# ReflowMaster.net
KiCad netlist of a schematic drawn in EAGLE
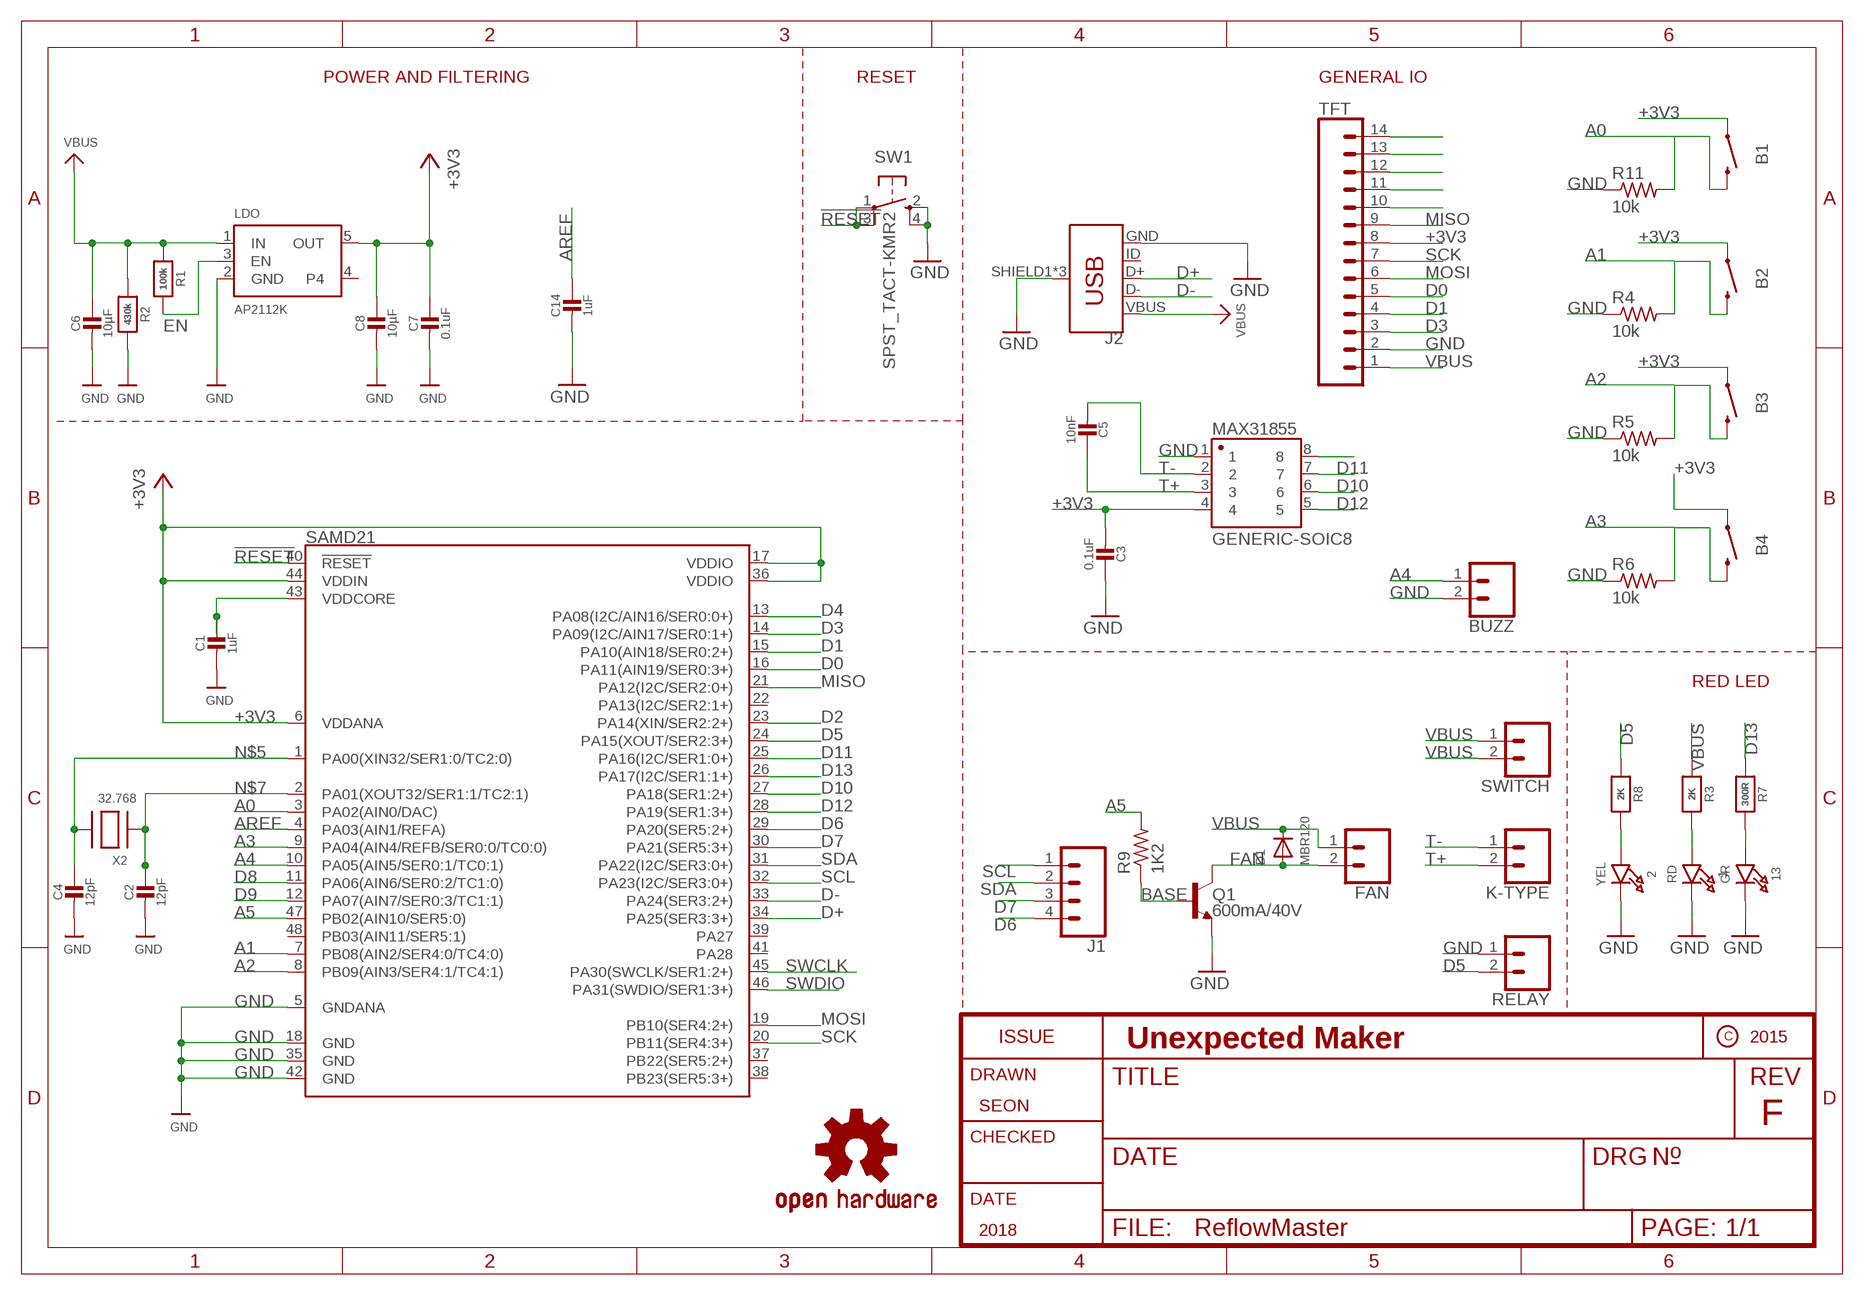
[diagram p0: schematic, sheet 1]

(export (version "E")
  (design (tool "Eeschema 10.0.6"))
  (components
    (comp (ref "1")
      (value "RD")
      (footprint "eagle-import:CHIPLED_0805_NOOUTLINE")
      (libsource (lib "eagle-import") (part "LED0805_NOOUTLINE"))
    )
    (comp (ref "2")
      (value "YEL")
      (footprint "eagle-import:CHIPLED_0805_NOOUTLINE")
      (libsource (lib "eagle-import") (part "LED0805_NOOUTLINE"))
    )
    (comp (ref "13")
      (value "GR")
      (footprint "eagle-import:CHIPLED_0805_NOOUTLINE")
      (libsource (lib "eagle-import") (part "LED0805_NOOUTLINE"))
    )
    (comp (ref "B1")
      (value "MOMENTARY-SWITCH-SPST-PTH-RIGHT-ANGLE-KIT")
      (footprint "eagle-import:TACTILE_SWITCH_PTH_RIGHT_ANGLE_KIT")
      (libsource (lib "eagle-import") (part "MOMENTARY-SWITCH-SPST-PTH-RIGHT-ANGLE-KIT"))
    )
    (comp (ref "B2")
      (value "MOMENTARY-SWITCH-SPST-PTH-RIGHT-ANGLE-KIT")
      (footprint "eagle-import:TACTILE_SWITCH_PTH_RIGHT_ANGLE_KIT")
      (libsource (lib "eagle-import") (part "MOMENTARY-SWITCH-SPST-PTH-RIGHT-ANGLE-KIT"))
    )
    (comp (ref "B3")
      (value "MOMENTARY-SWITCH-SPST-PTH-RIGHT-ANGLE-KIT")
      (footprint "eagle-import:TACTILE_SWITCH_PTH_RIGHT_ANGLE_KIT")
      (libsource (lib "eagle-import") (part "MOMENTARY-SWITCH-SPST-PTH-RIGHT-ANGLE-KIT"))
    )
    (comp (ref "B4")
      (value "MOMENTARY-SWITCH-SPST-PTH-RIGHT-ANGLE-KIT")
      (footprint "eagle-import:TACTILE_SWITCH_PTH_RIGHT_ANGLE_KIT")
      (libsource (lib "eagle-import") (part "MOMENTARY-SWITCH-SPST-PTH-RIGHT-ANGLE-KIT"))
    )
    (comp (ref "BUZZ")
      (value "CONN_02")
      (footprint "eagle-import:1X02")
      (libsource (lib "eagle-import") (part "CONN_02"))
    )
    (comp (ref "C1")
      (value "1uF")
      (footprint "eagle-import:0805-NO")
      (libsource (lib "eagle-import") (part "CAP_CERAMIC0805-NOOUTLINE"))
    )
    (comp (ref "C2")
      (value "12pF")
      (footprint "eagle-import:0805-NO")
      (libsource (lib "eagle-import") (part "CAP_CERAMIC0805-NOOUTLINE"))
    )
    (comp (ref "C3")
      (value "0.1uF")
      (footprint "eagle-import:0805-NO")
      (libsource (lib "eagle-import") (part "CAP_CERAMIC0805-NOOUTLINE"))
    )
    (comp (ref "C4")
      (value "12pF")
      (footprint "eagle-import:0805-NO")
      (libsource (lib "eagle-import") (part "CAP_CERAMIC0805-NOOUTLINE"))
    )
    (comp (ref "C5")
      (value "10nF")
      (footprint "eagle-import:0805-NO")
      (libsource (lib "eagle-import") (part "CAP_CERAMIC0805-NOOUTLINE"))
    )
    (comp (ref "C6")
      (value "10µF")
      (footprint "eagle-import:0805-NO")
      (libsource (lib "eagle-import") (part "CAP_CERAMIC0805-NOOUTLINE"))
    )
    (comp (ref "C7")
      (value "0.1uF")
      (footprint "eagle-import:0805-NO")
      (libsource (lib "eagle-import") (part "CAP_CERAMIC0805-NOOUTLINE"))
    )
    (comp (ref "C8")
      (value "10µF")
      (footprint "eagle-import:0805-NO")
      (libsource (lib "eagle-import") (part "CAP_CERAMIC0805-NOOUTLINE"))
    )
    (comp (ref "C14")
      (value "1uF")
      (footprint "eagle-import:0805-NO")
      (libsource (lib "eagle-import") (part "CAP_CERAMIC0805-NOOUTLINE"))
    )
    (comp (ref "D1")
      (value "MBR120")
      (footprint "eagle-import:SOD-123")
      (libsource (lib "eagle-import") (part "DIODESOD-123"))
    )
    (comp (ref "FAN")
      (value "CONN_02")
      (footprint "eagle-import:1X02")
      (libsource (lib "eagle-import") (part "CONN_02"))
    )
    (comp (ref "J1")
      (value "CONN_041X04_NO_SILK")
      (footprint "eagle-import:1X04_NO_SILK")
      (libsource (lib "eagle-import") (part "CONN_041X04_NO_SILK"))
    )
    (comp (ref "J2")
      (value "USB_MICRO-B_FEMALE-SMT")
      (footprint "eagle-import:USB-B-MICRO-SMD")
      (libsource (lib "eagle-import") (part "USB_MICRO-B_FEMALE-SMT"))
    )
    (comp (ref "K-TYPE")
      (value "CONN_02")
      (footprint "eagle-import:1X02")
      (libsource (lib "eagle-import") (part "CONN_02"))
    )
    (comp (ref "LDO")
      (value "AP2112K")
      (footprint "eagle-import:SOT23-5")
      (libsource (lib "eagle-import") (part "VREG_SOT23-5"))
    )
    (comp (ref "LOGO1")
      (value "OSHW-LOGOS")
      (footprint "eagle-import:OSHW-LOGO-S")
      (libsource (lib "eagle-import") (part "OSHW-LOGOS"))
    )
    (comp (ref "MAX31855")
      (value "GENERIC-SOIC8")
      (footprint "eagle-import:SO08-UNIVERSAL")
      (libsource (lib "eagle-import") (part "GENERIC-SOIC8"))
    )
    (comp (ref "Q1")
      (value "600mA/40V")
      (footprint "eagle-import:SOT23-3")
      (libsource (lib "eagle-import") (part "TRANS_NPN-MMBT2222AL"))
    )
    (comp (ref "R1")
      (value "100k")
      (footprint "eagle-import:0805-NO")
      (libsource (lib "eagle-import") (part "RESISTOR0805_NOOUTLINE"))
    )
    (comp (ref "R2")
      (value "430k")
      (footprint "eagle-import:0805-NO")
      (libsource (lib "eagle-import") (part "RESISTOR0805_NOOUTLINE"))
    )
    (comp (ref "R3")
      (value "2K")
      (footprint "eagle-import:0805-NO")
      (libsource (lib "eagle-import") (part "RESISTOR0805_NOOUTLINE"))
    )
    (comp (ref "R4")
      (value "10k")
      (footprint "eagle-import:R0805")
      (libsource (lib "eagle-import") (part "R-US_R0805"))
    )
    (comp (ref "R5")
      (value "10k")
      (footprint "eagle-import:R0805")
      (libsource (lib "eagle-import") (part "R-US_R0805"))
    )
    (comp (ref "R6")
      (value "10k")
      (footprint "eagle-import:R0805")
      (libsource (lib "eagle-import") (part "R-US_R0805"))
    )
    (comp (ref "R7")
      (value "300R")
      (footprint "eagle-import:0805-NO")
      (libsource (lib "eagle-import") (part "RESISTOR0805_NOOUTLINE"))
    )
    (comp (ref "R8")
      (value "2K")
      (footprint "eagle-import:0805-NO")
      (libsource (lib "eagle-import") (part "RESISTOR0805_NOOUTLINE"))
    )
    (comp (ref "R9")
      (value "1K2")
      (footprint "eagle-import:R0805")
      (libsource (lib "eagle-import") (part "R-US_R0805"))
    )
    (comp (ref "R11")
      (value "10k")
      (footprint "eagle-import:R0805")
      (libsource (lib "eagle-import") (part "R-US_R0805"))
    )
    (comp (ref "RELAY")
      (value "CONN_02")
      (footprint "eagle-import:1X02")
      (libsource (lib "eagle-import") (part "CONN_02"))
    )
    (comp (ref "SAMD21")
      (value "ATSAMD21G-A")
      (footprint "eagle-import:TQFP-48")
      (libsource (lib "eagle-import") (part "ATSAMD21G-A"))
    )
    (comp (ref "SW1")
      (value "SPST_TACT-KMR2")
      (footprint "eagle-import:KMR2")
      (libsource (lib "eagle-import") (part "SPST_TACT-KMR2"))
    )
    (comp (ref "SWITCH")
      (value "CONN_02")
      (footprint "eagle-import:1X02")
      (libsource (lib "eagle-import") (part "CONN_02"))
    )
    (comp (ref "TFT")
      (value "CONN_14NO_SILK")
      (footprint "eagle-import:1X14_NO_SILK")
      (libsource (lib "eagle-import") (part "CONN_14NO_SILK"))
    )
    (comp (ref "X2")
      (value "32.768")
      (footprint "eagle-import:XTAL3215")
      (libsource (lib "eagle-import") (part "XTAL-3.2X1.5"))
    )
  )
  (nets
    (net (code "1") (name "+3V3") (class "Default")
      (node (ref "B1") (pin "1") (pinfunction "1_1") (pintype "passive"))
      (node (ref "B2") (pin "1") (pinfunction "1_1") (pintype "passive"))
      (node (ref "B3") (pin "1") (pinfunction "1_1") (pintype "passive"))
      (node (ref "B4") (pin "1") (pinfunction "1_1") (pintype "passive"))
      (node (ref "C3") (pin "2") (pinfunction "2_2") (pintype "passive"))
      (node (ref "C7") (pin "1") (pinfunction "1_1") (pintype "passive"))
      (node (ref "C8") (pin "1") (pinfunction "1_1") (pintype "passive"))
      (node (ref "LDO") (pin "5") (pinfunction "OUT_5") (pintype "power_in"))
      (node (ref "MAX31855") (pin "4") (pinfunction "4_4") (pintype "bidirectional"))
      (node (ref "SAMD21") (pin "17") (pinfunction "VDDIO_17") (pintype "bidirectional"))
      (node (ref "SAMD21") (pin "36") (pinfunction "VDDIO_36") (pintype "bidirectional"))
      (node (ref "SAMD21") (pin "44") (pinfunction "VDDIN_44") (pintype "bidirectional"))
      (node (ref "SAMD21") (pin "6") (pinfunction "VDDANA_6") (pintype "bidirectional"))
      (node (ref "TFT") (pin "8") (pinfunction "8_8") (pintype "passive"))
    )
    (net (code "2") (name "/A0") (class "Default")
      (node (ref "B1") (pin "2") (pinfunction "2_2") (pintype "passive"))
      (node (ref "R11") (pin "2") (pinfunction "2_2") (pintype "passive"))
      (node (ref "SAMD21") (pin "3") (pinfunction "PA02(AIN0/DAC)_3") (pintype "bidirectional"))
    )
    (net (code "3") (name "/A1") (class "Default")
      (node (ref "B2") (pin "2") (pinfunction "2_2") (pintype "passive"))
      (node (ref "R4") (pin "2") (pinfunction "2_2") (pintype "passive"))
      (node (ref "SAMD21") (pin "7") (pinfunction "PB08(AIN2/SER4:0/TC4:0)_7") (pintype "bidirectional"))
    )
    (net (code "4") (name "/A2") (class "Default")
      (node (ref "B3") (pin "2") (pinfunction "2_2") (pintype "passive"))
      (node (ref "R5") (pin "2") (pinfunction "2_2") (pintype "passive"))
      (node (ref "SAMD21") (pin "8") (pinfunction "PB09(AIN3/SER4:1/TC4:1)_8") (pintype "bidirectional"))
    )
    (net (code "5") (name "/A3") (class "Default")
      (node (ref "B4") (pin "2") (pinfunction "2_2") (pintype "passive"))
      (node (ref "R6") (pin "2") (pinfunction "2_2") (pintype "passive"))
      (node (ref "SAMD21") (pin "9") (pinfunction "PA04(AIN4/REFB/SER0:0/TC0:0)_9") (pintype "bidirectional"))
    )
    (net (code "6") (name "/A4") (class "Default")
      (node (ref "BUZZ") (pin "1") (pinfunction "1_1") (pintype "passive"))
      (node (ref "SAMD21") (pin "10") (pinfunction "PA05(AIN5/SER0:1/TC0:1)_10") (pintype "bidirectional"))
    )
    (net (code "7") (name "/A5") (class "Default")
      (node (ref "R9") (pin "2") (pinfunction "2_2") (pintype "passive"))
      (node (ref "SAMD21") (pin "47") (pinfunction "PB02(AIN10/SER5:0)_47") (pintype "bidirectional"))
    )
    (net (code "8") (name "/AREF") (class "Default")
      (node (ref "C14") (pin "1") (pinfunction "1_1") (pintype "passive"))
      (node (ref "SAMD21") (pin "4") (pinfunction "PA03(AIN1/REFA)_4") (pintype "bidirectional"))
    )
    (net (code "9") (name "/BASE") (class "Default")
      (node (ref "Q1") (pin "1") (pinfunction "B_1") (pintype "passive"))
      (node (ref "R9") (pin "1") (pinfunction "1_1") (pintype "passive"))
    )
    (net (code "10") (name "/D+") (class "Default")
      (node (ref "J2") (pin "D+") (pinfunction "D+_D+") (pintype "bidirectional"))
      (node (ref "SAMD21") (pin "34") (pinfunction "PA25(SER3:3+)_34") (pintype "bidirectional"))
    )
    (net (code "11") (name "/D-") (class "Default")
      (node (ref "J2") (pin "D-") (pinfunction "D-_D-") (pintype "bidirectional"))
      (node (ref "SAMD21") (pin "33") (pinfunction "PA24(SER3:2+)_33") (pintype "bidirectional"))
    )
    (net (code "12") (name "/D0") (class "Default")
      (node (ref "SAMD21") (pin "16") (pinfunction "PA11(AIN19/SER0:3+)_16") (pintype "bidirectional"))
      (node (ref "TFT") (pin "5") (pinfunction "5_5") (pintype "passive"))
    )
    (net (code "13") (name "/D1") (class "Default")
      (node (ref "SAMD21") (pin "15") (pinfunction "PA10(AIN18/SER0:2+)_15") (pintype "bidirectional"))
      (node (ref "TFT") (pin "4") (pinfunction "4_4") (pintype "passive"))
    )
    (net (code "14") (name "/D2") (class "Default")
      (node (ref "SAMD21") (pin "23") (pinfunction "PA14(XIN/SER2:2+)_23") (pintype "bidirectional"))
    )
    (net (code "15") (name "/D3") (class "Default")
      (node (ref "SAMD21") (pin "14") (pinfunction "PA09(I2C/AIN17/SER0:1+)_14") (pintype "bidirectional"))
      (node (ref "TFT") (pin "3") (pinfunction "3_3") (pintype "passive"))
    )
    (net (code "16") (name "/D4") (class "Default")
      (node (ref "SAMD21") (pin "13") (pinfunction "PA08(I2C/AIN16/SER0:0+)_13") (pintype "bidirectional"))
    )
    (net (code "17") (name "/D5") (class "Default")
      (node (ref "R8") (pin "1") (pinfunction "1_1") (pintype "passive"))
      (node (ref "RELAY") (pin "2") (pinfunction "2_2") (pintype "passive"))
      (node (ref "SAMD21") (pin "24") (pinfunction "PA15(XOUT/SER2:3+)_24") (pintype "bidirectional"))
    )
    (net (code "18") (name "/D6") (class "Default")
      (node (ref "J1") (pin "4") (pinfunction "4_4") (pintype "passive"))
      (node (ref "SAMD21") (pin "29") (pinfunction "PA20(SER5:2+)_29") (pintype "bidirectional"))
    )
    (net (code "19") (name "/D7") (class "Default")
      (node (ref "J1") (pin "3") (pinfunction "3_3") (pintype "passive"))
      (node (ref "SAMD21") (pin "30") (pinfunction "PA21(SER5:3+)_30") (pintype "bidirectional"))
    )
    (net (code "20") (name "/D8") (class "Default")
      (node (ref "SAMD21") (pin "11") (pinfunction "PA06(AIN6/SER0:2/TC1:0)_11") (pintype "bidirectional"))
    )
    (net (code "21") (name "/D9") (class "Default")
      (node (ref "SAMD21") (pin "12") (pinfunction "PA07(AIN7/SER0:3/TC1:1)_12") (pintype "bidirectional"))
    )
    (net (code "22") (name "/D10") (class "Default")
      (node (ref "MAX31855") (pin "6") (pinfunction "6_6") (pintype "bidirectional"))
      (node (ref "SAMD21") (pin "27") (pinfunction "PA18(SER1:2+)_27") (pintype "bidirectional"))
    )
    (net (code "23") (name "/D11") (class "Default")
      (node (ref "MAX31855") (pin "7") (pinfunction "7_7") (pintype "bidirectional"))
      (node (ref "SAMD21") (pin "25") (pinfunction "PA16(I2C/SER1:0+)_25") (pintype "bidirectional"))
    )
    (net (code "24") (name "/D12") (class "Default")
      (node (ref "MAX31855") (pin "5") (pinfunction "5_5") (pintype "bidirectional"))
      (node (ref "SAMD21") (pin "28") (pinfunction "PA19(SER1:3+)_28") (pintype "bidirectional"))
    )
    (net (code "25") (name "/D13") (class "Default")
      (node (ref "R7") (pin "1") (pinfunction "1_1") (pintype "passive"))
      (node (ref "SAMD21") (pin "26") (pinfunction "PA17(I2C/SER1:1+)_26") (pintype "bidirectional"))
    )
    (net (code "26") (name "/EN") (class "Default")
      (node (ref "LDO") (pin "3") (pinfunction "EN_3") (pintype "input"))
      (node (ref "R1") (pin "2") (pinfunction "2_2") (pintype "passive"))
    )
    (net (code "27") (name "/FAN") (class "Default")
      (node (ref "D1") (pin "A") (pinfunction "A_A") (pintype "passive"))
      (node (ref "FAN") (pin "2") (pinfunction "2_2") (pintype "passive"))
      (node (ref "Q1") (pin "3") (pinfunction "C_3") (pintype "passive"))
    )
    (net (code "28") (name "/MISO") (class "Default")
      (node (ref "SAMD21") (pin "21") (pinfunction "PA12(I2C/SER2:0+)_21") (pintype "bidirectional"))
      (node (ref "TFT") (pin "9") (pinfunction "9_9") (pintype "passive"))
    )
    (net (code "29") (name "/MOSI") (class "Default")
      (node (ref "SAMD21") (pin "19") (pinfunction "PB10(SER4:2+)_19") (pintype "bidirectional"))
      (node (ref "TFT") (pin "6") (pinfunction "6_6") (pintype "passive"))
    )
    (net (code "30") (name "/N$5") (class "Default")
      (node (ref "C4") (pin "1") (pinfunction "1_1") (pintype "passive"))
      (node (ref "SAMD21") (pin "1") (pinfunction "PA00(XIN32/SER1:0/TC2:0)_1") (pintype "bidirectional"))
      (node (ref "X2") (pin "P$2") (pinfunction "P$2_P$2") (pintype "bidirectional"))
    )
    (net (code "31") (name "/N$7") (class "Default")
      (node (ref "C2") (pin "1") (pinfunction "1_1") (pintype "passive"))
      (node (ref "SAMD21") (pin "2") (pinfunction "PA01(XOUT32/SER1:1/TC2:1)_2") (pintype "bidirectional"))
      (node (ref "X2") (pin "P$1") (pinfunction "P$1_P$1") (pintype "bidirectional"))
    )
    (net (code "32") (name "/SCK") (class "Default")
      (node (ref "SAMD21") (pin "20") (pinfunction "PB11(SER4:3+)_20") (pintype "bidirectional"))
      (node (ref "TFT") (pin "7") (pinfunction "7_7") (pintype "passive"))
    )
    (net (code "33") (name "/SCL") (class "Default")
      (node (ref "J1") (pin "1") (pinfunction "1_1") (pintype "passive"))
      (node (ref "SAMD21") (pin "32") (pinfunction "PA23(I2C/SER3:0+)_32") (pintype "bidirectional"))
    )
    (net (code "34") (name "/SDA") (class "Default")
      (node (ref "J1") (pin "2") (pinfunction "2_2") (pintype "passive"))
      (node (ref "SAMD21") (pin "31") (pinfunction "PA22(I2C/SER3:0+)_31") (pintype "bidirectional"))
    )
    (net (code "35") (name "/SWCLK") (class "Default")
      (node (ref "SAMD21") (pin "45") (pinfunction "PA30(SWCLK/SER1:2+)_45") (pintype "bidirectional"))
    )
    (net (code "36") (name "/SWDIO") (class "Default")
      (node (ref "SAMD21") (pin "46") (pinfunction "PA31(SWDIO/SER1:3+)_46") (pintype "bidirectional"))
    )
    (net (code "37") (name "/T+") (class "Default")
      (node (ref "C5") (pin "1") (pinfunction "1_1") (pintype "passive"))
      (node (ref "K-TYPE") (pin "2") (pinfunction "2_2") (pintype "passive"))
      (node (ref "MAX31855") (pin "3") (pinfunction "3_3") (pintype "bidirectional"))
    )
    (net (code "38") (name "/T-") (class "Default")
      (node (ref "C5") (pin "2") (pinfunction "2_2") (pintype "passive"))
      (node (ref "K-TYPE") (pin "1") (pinfunction "1_1") (pintype "passive"))
      (node (ref "MAX31855") (pin "2") (pinfunction "2_2") (pintype "bidirectional"))
    )
    (net (code "39") (name "/~{RESET}") (class "Default")
      (node (ref "SAMD21") (pin "40") (pinfunction "~{RESET}_40") (pintype "bidirectional"))
      (node (ref "SW1") (pin "1") (pinfunction "P_1") (pintype "passive"))
      (node (ref "SW1") (pin "3") (pinfunction "P1_3") (pintype "passive"))
    )
    (net (code "40") (name "GND") (class "Default")
      (node (ref "1") (pin "C") (pinfunction "C_C") (pintype "passive"))
      (node (ref "13") (pin "C") (pinfunction "C_C") (pintype "passive"))
      (node (ref "2") (pin "C") (pinfunction "C_C") (pintype "passive"))
      (node (ref "BUZZ") (pin "2") (pinfunction "2_2") (pintype "passive"))
      (node (ref "C1") (pin "2") (pinfunction "2_2") (pintype "passive"))
      (node (ref "C14") (pin "2") (pinfunction "2_2") (pintype "passive"))
      (node (ref "C2") (pin "2") (pinfunction "2_2") (pintype "passive"))
      (node (ref "C3") (pin "1") (pinfunction "1_1") (pintype "passive"))
      (node (ref "C4") (pin "2") (pinfunction "2_2") (pintype "passive"))
      (node (ref "C6") (pin "2") (pinfunction "2_2") (pintype "passive"))
      (node (ref "C7") (pin "2") (pinfunction "2_2") (pintype "passive"))
      (node (ref "C8") (pin "2") (pinfunction "2_2") (pintype "passive"))
      (node (ref "J2") (pin "GND") (pinfunction "GND_GND") (pintype "power_in"))
      (node (ref "J2") (pin "SHIELD1") (pinfunction "SHIELD_SHIELD1") (pintype "bidirectional"))
      (node (ref "J2") (pin "SHIELD2") (pinfunction "SHIELD_SHIELD2") (pintype "bidirectional"))
      (node (ref "J2") (pin "SHIELD3") (pinfunction "SHIELD_SHIELD3") (pintype "bidirectional"))
      (node (ref "LDO") (pin "2") (pinfunction "GND_2") (pintype "power_in"))
      (node (ref "MAX31855") (pin "1") (pinfunction "1_1") (pintype "bidirectional"))
      (node (ref "Q1") (pin "2") (pinfunction "E_2") (pintype "passive"))
      (node (ref "R11") (pin "1") (pinfunction "1_1") (pintype "passive"))
      (node (ref "R2") (pin "2") (pinfunction "2_2") (pintype "passive"))
      (node (ref "R4") (pin "1") (pinfunction "1_1") (pintype "passive"))
      (node (ref "R5") (pin "1") (pinfunction "1_1") (pintype "passive"))
      (node (ref "R6") (pin "1") (pinfunction "1_1") (pintype "passive"))
      (node (ref "RELAY") (pin "1") (pinfunction "1_1") (pintype "passive"))
      (node (ref "SAMD21") (pin "18") (pinfunction "GND_18") (pintype "bidirectional"))
      (node (ref "SAMD21") (pin "35") (pinfunction "GND_35") (pintype "bidirectional"))
      (node (ref "SAMD21") (pin "42") (pinfunction "GND_42") (pintype "bidirectional"))
      (node (ref "SAMD21") (pin "5") (pinfunction "GNDANA_5") (pintype "bidirectional"))
      (node (ref "SW1") (pin "2") (pinfunction "S_2") (pintype "passive"))
      (node (ref "SW1") (pin "4") (pinfunction "S1_4") (pintype "passive"))
      (node (ref "TFT") (pin "2") (pinfunction "2_2") (pintype "passive"))
    )
    (net (code "41") (name "Net-(1-PadA)") (class "Default")
      (node (ref "1") (pin "A") (pinfunction "A_A") (pintype "passive"))
      (node (ref "R3") (pin "2") (pinfunction "2_2") (pintype "passive"))
    )
    (net (code "42") (name "Net-(2-PadA)") (class "Default")
      (node (ref "2") (pin "A") (pinfunction "A_A") (pintype "passive"))
      (node (ref "R8") (pin "2") (pinfunction "2_2") (pintype "passive"))
    )
    (net (code "43") (name "Net-(13-PadA)") (class "Default")
      (node (ref "13") (pin "A") (pinfunction "A_A") (pintype "passive"))
      (node (ref "R7") (pin "2") (pinfunction "2_2") (pintype "passive"))
    )
    (net (code "44") (name "Net-(SAMD21-VDDCORE)") (class "Default")
      (node (ref "C1") (pin "1") (pinfunction "1_1") (pintype "passive"))
      (node (ref "SAMD21") (pin "43") (pinfunction "VDDCORE_43") (pintype "bidirectional"))
    )
    (net (code "45") (name "VBUS") (class "Default")
      (node (ref "C6") (pin "1") (pinfunction "1_1") (pintype "passive"))
      (node (ref "D1") (pin "C") (pinfunction "C_C") (pintype "passive"))
      (node (ref "FAN") (pin "1") (pinfunction "1_1") (pintype "passive"))
      (node (ref "J2") (pin "VBUS") (pinfunction "VBUS_VBUS") (pintype "power_in"))
      (node (ref "LDO") (pin "1") (pinfunction "IN_1") (pintype "power_in"))
      (node (ref "R1") (pin "1") (pinfunction "1_1") (pintype "passive"))
      (node (ref "R2") (pin "1") (pinfunction "1_1") (pintype "passive"))
      (node (ref "R3") (pin "1") (pinfunction "1_1") (pintype "passive"))
      (node (ref "SWITCH") (pin "1") (pinfunction "1_1") (pintype "passive"))
      (node (ref "SWITCH") (pin "2") (pinfunction "2_2") (pintype "passive"))
      (node (ref "TFT") (pin "1") (pinfunction "1_1") (pintype "passive"))
    )
    (net (code "46") (name "unconnected-(J2-PadID)") (class "Default")
      (node (ref "J2") (pin "ID") (pinfunction "ID_ID") (pintype "bidirectional"))
    )
    (net (code "47") (name "unconnected-(LDO-P4-Pad4)") (class "Default")
      (node (ref "LDO") (pin "4") (pinfunction "P4_4") (pintype "bidirectional"))
    )
    (net (code "48") (name "unconnected-(MAX31855-Pad8)") (class "Default")
      (node (ref "MAX31855") (pin "8") (pinfunction "8_8") (pintype "bidirectional"))
    )
    (net (code "49") (name "unconnected-(SAMD21-PA13(I2C{slash}SER2:1+)-Pad22)") (class "Default")
      (node (ref "SAMD21") (pin "22") (pinfunction "PA13(I2C/SER2:1+)_22") (pintype "bidirectional"))
    )
    (net (code "50") (name "unconnected-(SAMD21-PA27-Pad39)") (class "Default")
      (node (ref "SAMD21") (pin "39") (pinfunction "PA27_39") (pintype "bidirectional"))
    )
    (net (code "51") (name "unconnected-(SAMD21-PA28-Pad41)") (class "Default")
      (node (ref "SAMD21") (pin "41") (pinfunction "PA28_41") (pintype "bidirectional"))
    )
    (net (code "52") (name "unconnected-(SAMD21-PB03(AIN11{slash}SER5:1)-Pad48)") (class "Default")
      (node (ref "SAMD21") (pin "48") (pinfunction "PB03(AIN11/SER5:1)_48") (pintype "bidirectional"))
    )
    (net (code "53") (name "unconnected-(SAMD21-PB22(SER5:2+)-Pad37)") (class "Default")
      (node (ref "SAMD21") (pin "37") (pinfunction "PB22(SER5:2+)_37") (pintype "bidirectional"))
    )
    (net (code "54") (name "unconnected-(SAMD21-PB23(SER5:3+)-Pad38)") (class "Default")
      (node (ref "SAMD21") (pin "38") (pinfunction "PB23(SER5:3+)_38") (pintype "bidirectional"))
    )
    (net (code "55") (name "unconnected-(TFT-Pad10)") (class "Default")
      (node (ref "TFT") (pin "10") (pinfunction "10_10") (pintype "passive"))
    )
    (net (code "56") (name "unconnected-(TFT-Pad11)") (class "Default")
      (node (ref "TFT") (pin "11") (pinfunction "11_11") (pintype "passive"))
    )
    (net (code "57") (name "unconnected-(TFT-Pad12)") (class "Default")
      (node (ref "TFT") (pin "12") (pinfunction "12_12") (pintype "passive"))
    )
    (net (code "58") (name "unconnected-(TFT-Pad13)") (class "Default")
      (node (ref "TFT") (pin "13") (pinfunction "13_13") (pintype "passive"))
    )
    (net (code "59") (name "unconnected-(TFT-Pad14)") (class "Default")
      (node (ref "TFT") (pin "14") (pinfunction "14_14") (pintype "passive"))
    )
  )
)
